# grvg-001.net
KiCad netlist of a schematic drawn in EAGLE
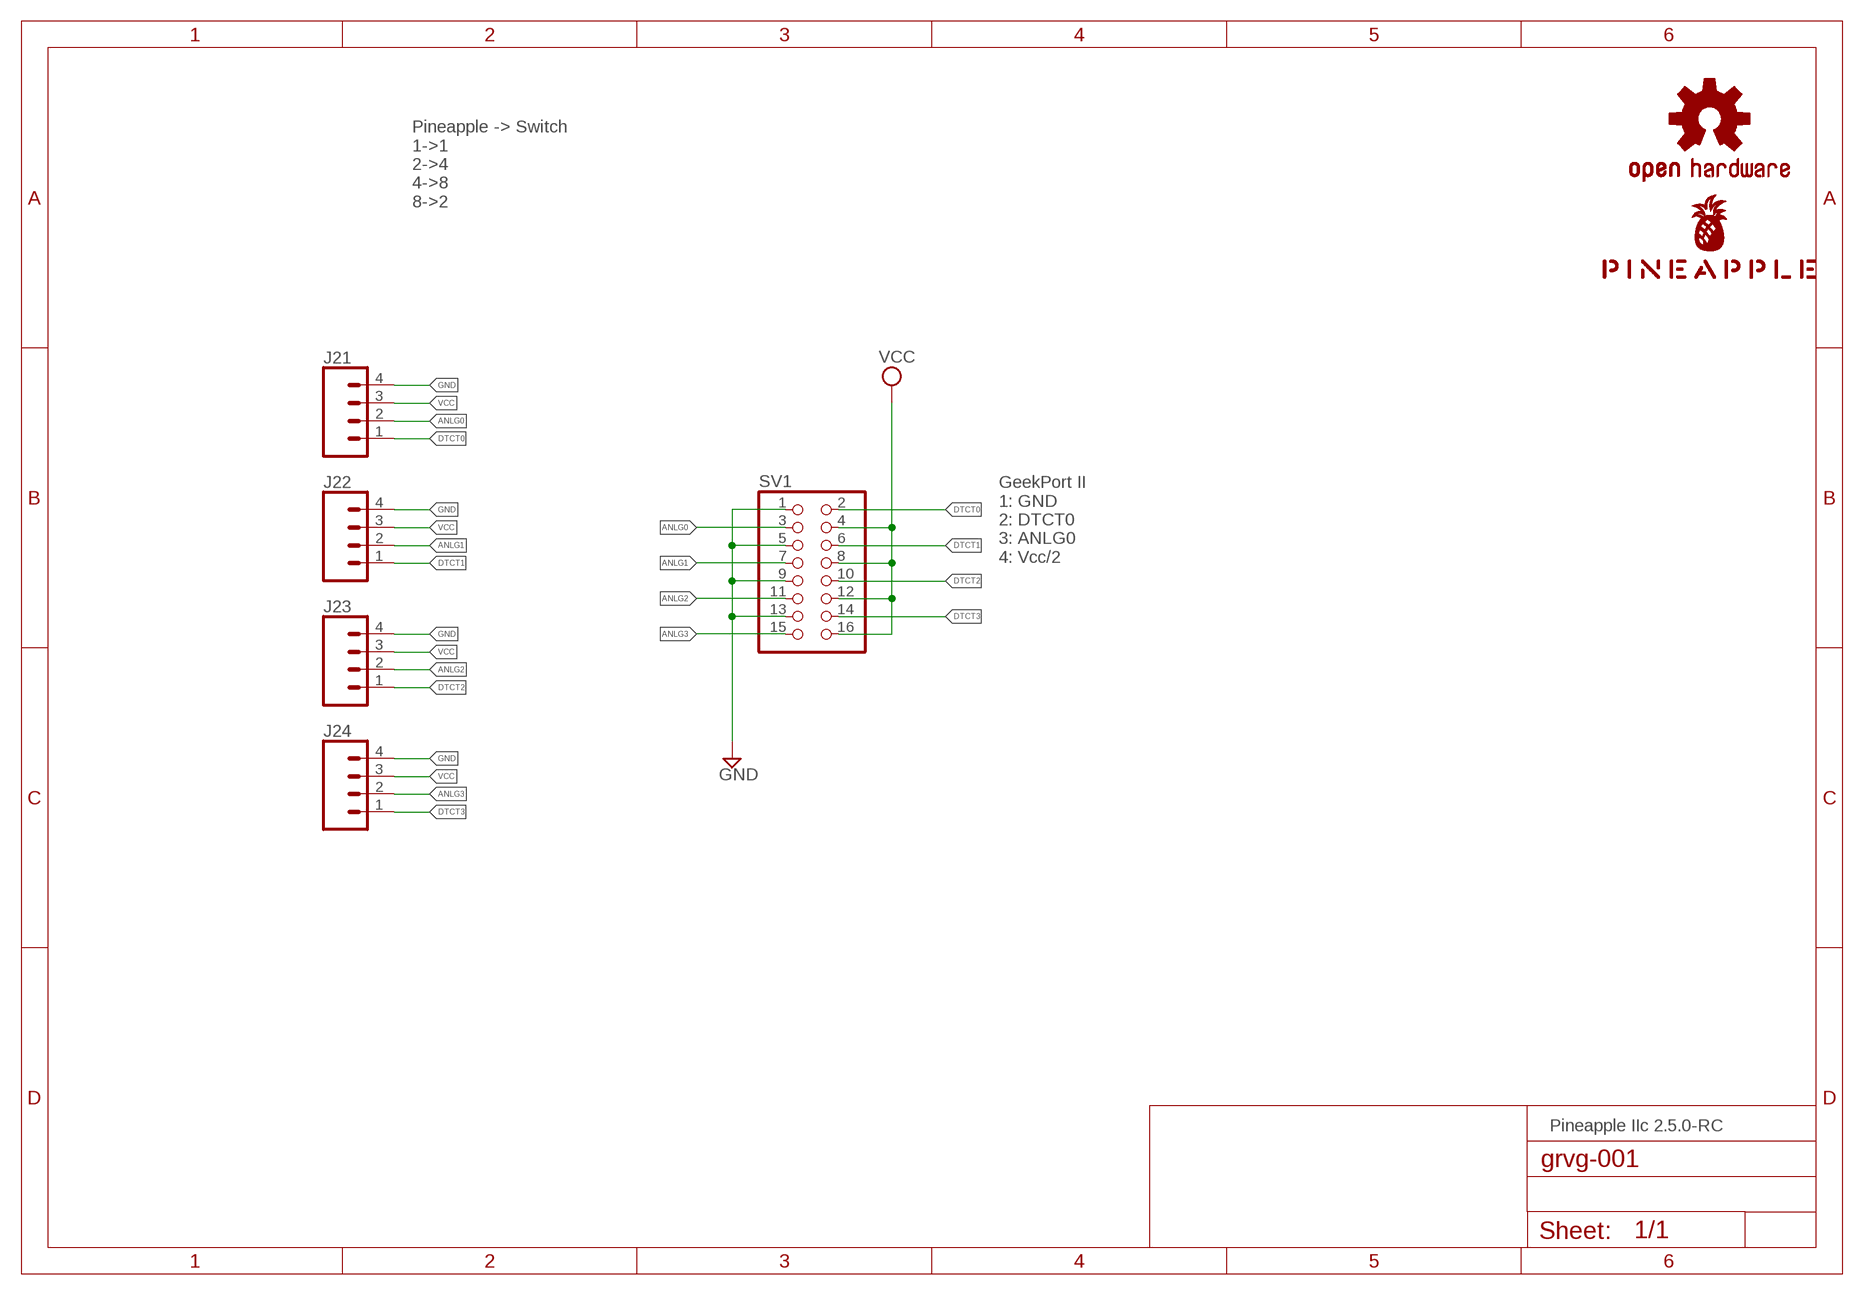
[diagram p0: schematic, sheet 1]

(export (version "E")
  (design (tool "Eeschema 10.0.6"))
  (components
    (comp (ref "J21")
      (value "CONN_04JST-PTH-VERT")
      (footprint "eagle-import:JST-4-PTH-VERT")
      (libsource (lib "eagle-import") (part "CONN_04JST-PTH-VERT"))
    )
    (comp (ref "J22")
      (value "CONN_04JST-PTH-VERT")
      (footprint "eagle-import:JST-4-PTH-VERT")
      (libsource (lib "eagle-import") (part "CONN_04JST-PTH-VERT"))
    )
    (comp (ref "J23")
      (value "CONN_04JST-PTH-VERT")
      (footprint "eagle-import:JST-4-PTH-VERT")
      (libsource (lib "eagle-import") (part "CONN_04JST-PTH-VERT"))
    )
    (comp (ref "J24")
      (value "CONN_04JST-PTH-VERT")
      (footprint "eagle-import:JST-4-PTH-VERT")
      (libsource (lib "eagle-import") (part "CONN_04JST-PTH-VERT"))
    )
    (comp (ref "LOGO1")
      (value "OSHW-LOGOS-COPPER")
      (footprint "eagle-import:OSHW-LOGO-S_COPPER")
      (libsource (lib "eagle-import") (part "OSHW-LOGOS-COPPER"))
    )
    (comp (ref "SV1")
      (value "PINHD-2X8")
      (footprint "eagle-import:2X08")
      (libsource (lib "eagle-import") (part "PINHD-2X8"))
    )
    (comp (ref "U$1")
      (value "PINEAPPLE450_SILK")
      (footprint "eagle-import:PINEAPPLE450_SILK")
      (libsource (lib "eagle-import") (part "PINEAPPLE450_SILK"))
    )
  )
  (nets
    (net (code "1") (name "ANLG0") (class "Default")
      (node (ref "J21") (pin "2") (pinfunction "2_2") (pintype "passive"))
      (node (ref "SV1") (pin "3") (pinfunction "3_3") (pintype "passive"))
    )
    (net (code "2") (name "ANLG1") (class "Default")
      (node (ref "J22") (pin "2") (pinfunction "2_2") (pintype "passive"))
      (node (ref "SV1") (pin "7") (pinfunction "7_7") (pintype "passive"))
    )
    (net (code "3") (name "ANLG2") (class "Default")
      (node (ref "J23") (pin "2") (pinfunction "2_2") (pintype "passive"))
      (node (ref "SV1") (pin "11") (pinfunction "11_11") (pintype "passive"))
    )
    (net (code "4") (name "ANLG3") (class "Default")
      (node (ref "J24") (pin "2") (pinfunction "2_2") (pintype "passive"))
      (node (ref "SV1") (pin "15") (pinfunction "15_15") (pintype "passive"))
    )
    (net (code "5") (name "DTCT0") (class "Default")
      (node (ref "J21") (pin "1") (pinfunction "1_1") (pintype "passive"))
      (node (ref "SV1") (pin "2") (pinfunction "2_2") (pintype "passive"))
    )
    (net (code "6") (name "DTCT1") (class "Default")
      (node (ref "J22") (pin "1") (pinfunction "1_1") (pintype "passive"))
      (node (ref "SV1") (pin "6") (pinfunction "6_6") (pintype "passive"))
    )
    (net (code "7") (name "DTCT2") (class "Default")
      (node (ref "J23") (pin "1") (pinfunction "1_1") (pintype "passive"))
      (node (ref "SV1") (pin "10") (pinfunction "10_10") (pintype "passive"))
    )
    (net (code "8") (name "DTCT3") (class "Default")
      (node (ref "J24") (pin "1") (pinfunction "1_1") (pintype "passive"))
      (node (ref "SV1") (pin "14") (pinfunction "14_14") (pintype "passive"))
    )
    (net (code "9") (name "GND") (class "Default")
      (node (ref "J21") (pin "4") (pinfunction "4_4") (pintype "passive"))
      (node (ref "J22") (pin "4") (pinfunction "4_4") (pintype "passive"))
      (node (ref "J23") (pin "4") (pinfunction "4_4") (pintype "passive"))
      (node (ref "J24") (pin "4") (pinfunction "4_4") (pintype "passive"))
      (node (ref "SV1") (pin "1") (pinfunction "1_1") (pintype "passive"))
      (node (ref "SV1") (pin "13") (pinfunction "13_13") (pintype "passive"))
      (node (ref "SV1") (pin "5") (pinfunction "5_5") (pintype "passive"))
      (node (ref "SV1") (pin "9") (pinfunction "9_9") (pintype "passive"))
    )
    (net (code "10") (name "VCC") (class "Default")
      (node (ref "J21") (pin "3") (pinfunction "3_3") (pintype "passive"))
      (node (ref "J22") (pin "3") (pinfunction "3_3") (pintype "passive"))
      (node (ref "J23") (pin "3") (pinfunction "3_3") (pintype "passive"))
      (node (ref "J24") (pin "3") (pinfunction "3_3") (pintype "passive"))
      (node (ref "SV1") (pin "12") (pinfunction "12_12") (pintype "passive"))
      (node (ref "SV1") (pin "16") (pinfunction "16_16") (pintype "passive"))
      (node (ref "SV1") (pin "4") (pinfunction "4_4") (pintype "passive"))
      (node (ref "SV1") (pin "8") (pinfunction "8_8") (pintype "passive"))
    )
  )
)
